# SWD.net
KiCad netlist of a schematic drawn in Altium Designer
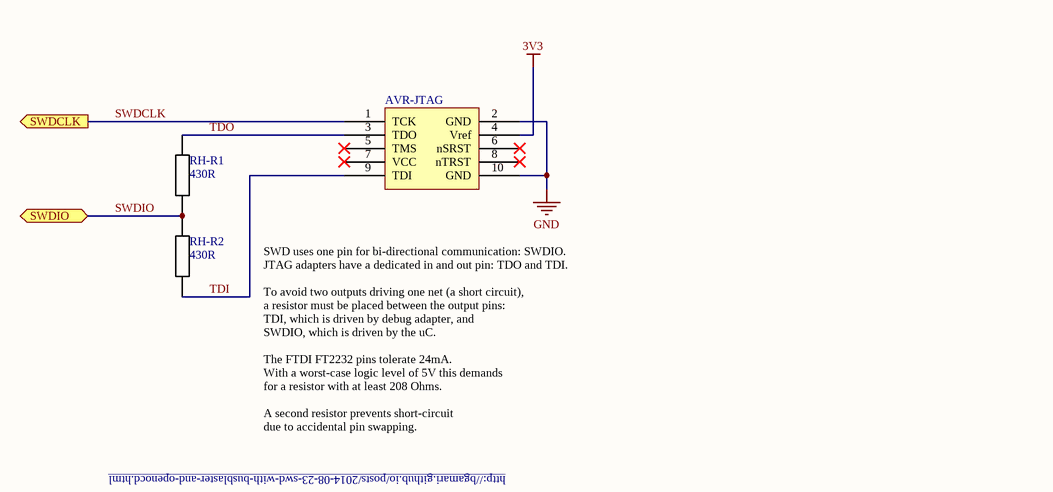
[diagram p0: SWD.SchDoc]

(export (version "E")
  (design (tool "Eeschema 10.0.6"))
  (components
    (comp (ref "AVR-JTAG")
      (value "AVR Style")
      (footprint "Header 2x5 IDC SMT")
      (libsource (lib "Headers") (part "Header JTAG AVR"))
    )
    (comp (ref "RH-R1")
      (value "430R")
      (footprint "R 0805 / 2012 wide")
      (libsource (lib "Core51822-related") (part "Resistor"))
    )
    (comp (ref "RH-R2")
      (value "430R")
      (footprint "R 0805 / 2012 wide")
      (libsource (lib "Core51822-related") (part "Resistor"))
    )
  )
  (nets
    (net (code "1") (name "/SWDCLK") (class "Default")
      (node (ref "AVR-JTAG") (pin "1") (pinfunction "TCK_1") (pintype "passive"))
    )
    (net (code "2") (name "/SWDIO") (class "Default")
      (node (ref "RH-R1") (pin "1") (pinfunction "1_1") (pintype "passive"))
      (node (ref "RH-R2") (pin "2") (pinfunction "2_2") (pintype "passive"))
    )
    (net (code "3") (name "/TDI") (class "Default")
      (node (ref "AVR-JTAG") (pin "9") (pinfunction "TDI_9") (pintype "passive"))
      (node (ref "RH-R2") (pin "1") (pinfunction "1_1") (pintype "passive"))
    )
    (net (code "4") (name "/TDO") (class "Default")
      (node (ref "AVR-JTAG") (pin "3") (pinfunction "TDO_3") (pintype "passive"))
      (node (ref "RH-R1") (pin "2") (pinfunction "2_2") (pintype "passive"))
    )
    (net (code "5") (name "3V3") (class "Default")
      (node (ref "AVR-JTAG") (pin "4") (pinfunction "Vref_4") (pintype "passive"))
    )
    (net (code "6") (name "GND") (class "Default")
      (node (ref "AVR-JTAG") (pin "10") (pinfunction "GND_10") (pintype "passive"))
      (node (ref "AVR-JTAG") (pin "2") (pinfunction "GND_2") (pintype "passive"))
    )
    (net (code "7") (name "unconnected-(AVR-JTAG-TMS-Pad5)") (class "Default")
      (node (ref "AVR-JTAG") (pin "5") (pinfunction "TMS_5") (pintype "passive+no_connect"))
    )
    (net (code "8") (name "unconnected-(AVR-JTAG-VCC-Pad7)") (class "Default")
      (node (ref "AVR-JTAG") (pin "7") (pinfunction "VCC_7") (pintype "passive+no_connect"))
    )
    (net (code "9") (name "unconnected-(AVR-JTAG-nSRST-Pad6)") (class "Default")
      (node (ref "AVR-JTAG") (pin "6") (pinfunction "nSRST_6") (pintype "passive+no_connect"))
    )
    (net (code "10") (name "unconnected-(AVR-JTAG-nTRST-Pad8)") (class "Default")
      (node (ref "AVR-JTAG") (pin "8") (pinfunction "nTRST_8") (pintype "passive+no_connect"))
    )
  )
)
